# Max3100Uart.net
KiCad netlist of a schematic drawn in Altium Designer
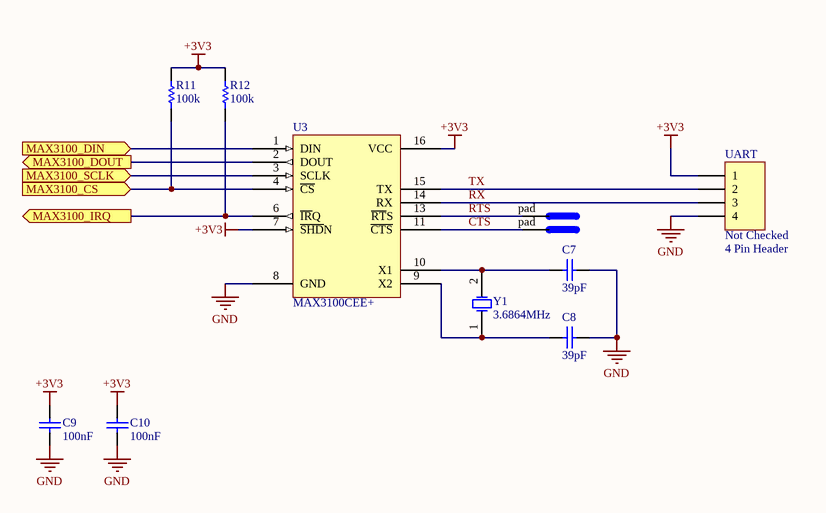
[diagram p0: Max3100Uart.SchDoc]

(export (version "E")
  (design (tool "Eeschema 10.0.6"))
  (components
    (comp (ref "C7")
      (value "39pF")
      (footprint "0603")
      (description "Capacitor")
      (fields (field (name "Comment") "Cap") (field (name "PUBLISHER") "Altium Limited"))
      (libsource (lib "Miscellaneous Devices") (part "Cap"))
    )
    (comp (ref "C8")
      (value "39pF")
      (footprint "0603")
      (description "Capacitor")
      (fields (field (name "Comment") "Cap") (field (name "PUBLISHER") "Altium Limited"))
      (libsource (lib "Miscellaneous Devices") (part "Cap"))
    )
    (comp (ref "C9")
      (value "100nF")
      (footprint "GRC PCB library:0603")
      (description "CAP CER .10UF 50V X5R 0603")
      (fields (field (name "MANUFACTURER") "Taiyo Yuden"))
      (libsource (lib "GRC sch library") (part "CP_100nF 0603"))
    )
    (comp (ref "C10")
      (value "100nF")
      (footprint "GRC PCB library:0603")
      (description "CAP CER .10UF 50V X5R 0603")
      (fields (field (name "MANUFACTURER") "Taiyo Yuden"))
      (libsource (lib "GRC sch library") (part "CP_100nF 0603"))
    )
    (comp (ref "CTS")
      (value "~")
      (footprint "PAD_ROUND")
      (description "Pad")
      (libsource (lib "GRC sch library") (part "JP_pad"))
    )
    (comp (ref "R11")
      (value "100k")
      (footprint "GRC PCB library:0603")
      (description "RES 100K OHM 1/10W 1% 0603 SMD")
      (fields (field (name "MANUFACTURER") "Yageo"))
      (libsource (lib "GRC sch library") (part "RS_100k 0603"))
    )
    (comp (ref "R12")
      (value "100k")
      (footprint "GRC PCB library:0603")
      (description "RES 100K OHM 1/10W 1% 0603 SMD")
      (fields (field (name "MANUFACTURER") "Yageo"))
      (libsource (lib "GRC sch library") (part "RS_100k 0603"))
    )
    (comp (ref "RTS")
      (value "~")
      (footprint "PAD_ROUND")
      (description "Pad")
      (libsource (lib "GRC sch library") (part "JP_pad"))
    )
    (comp (ref "U3")
      (value "MAX3100CEE+")
      (footprint "QSOP16_MAX3100")
      (description "SPI UART")
      (libsource (lib "GRC sch library") (part "IC_MAX3100"))
    )
    (comp (ref "UART")
      (value "4 Pin Header")
      (footprint "CONN_4X1_SMT_RA_1.25MM")
      (description "CONN HDR VERT 4POS .100\" SNGL")
      (fields (field (name "MANUFACTURER") "Molex") (field (name "VERIFY") "Not Checked"))
      (libsource (lib "GRC sch library") (part "JP_4PIN HDR_SMT_RA_MOLEX_1"))
    )
    (comp (ref "Y1")
      (value "3.6864MHz")
      (footprint "HC49/4h_SMX")
      (description "Crystal Oscillator")
      (fields (field (name "MANUFACTURER") "ECS") (field (name "PUBLISHER") "Altium Limited"))
      (libsource (lib "Miscellaneous Devices") (part "XTAL"))
    )
  )
  (nets
    (net (code "1") (name "+3V3") (class "Default")
      (node (ref "C10") (pin "2") (pinfunction "2_2") (pintype "passive"))
      (node (ref "C9") (pin "2") (pinfunction "2_2") (pintype "passive"))
      (node (ref "R11") (pin "2") (pinfunction "2_2") (pintype "passive"))
      (node (ref "R12") (pin "2") (pinfunction "2_2") (pintype "passive"))
      (node (ref "U3") (pin "16") (pinfunction "VCC_16") (pintype "power_in"))
      (node (ref "U3") (pin "7") (pinfunction "~{SHD}N_7") (pintype "input"))
      (node (ref "UART") (pin "1") (pinfunction "1_1") (pintype "passive"))
    )
    (net (code "2") (name "/CTS") (class "Default")
      (node (ref "CTS") (pin "pad") (pintype "passive"))
      (node (ref "U3") (pin "11") (pinfunction "~{CTS}_11") (pintype "passive"))
    )
    (net (code "3") (name "/MAX3100_CS") (class "Default")
      (node (ref "R11") (pin "1") (pinfunction "1_1") (pintype "passive"))
      (node (ref "U3") (pin "4") (pinfunction "~{CS}_4") (pintype "input"))
    )
    (net (code "4") (name "/MAX3100_DIN") (class "Default")
      (node (ref "U3") (pin "1") (pinfunction "DIN_1") (pintype "input"))
    )
    (net (code "5") (name "/MAX3100_DOUT") (class "Default")
      (node (ref "U3") (pin "2") (pinfunction "DOUT_2") (pintype "output"))
    )
    (net (code "6") (name "/MAX3100_IRQ") (class "Default")
      (node (ref "R12") (pin "1") (pinfunction "1_1") (pintype "passive"))
      (node (ref "U3") (pin "6") (pinfunction "~{IR}Q_6") (pintype "output"))
    )
    (net (code "7") (name "/MAX3100_SCLK") (class "Default")
      (node (ref "U3") (pin "3") (pinfunction "SCLK_3") (pintype "input"))
    )
    (net (code "8") (name "/RTS") (class "Default")
      (node (ref "RTS") (pin "pad") (pintype "passive"))
      (node (ref "U3") (pin "13") (pinfunction "~{RT}S_13") (pintype "passive"))
    )
    (net (code "9") (name "/RX") (class "Default")
      (node (ref "U3") (pin "14") (pinfunction "RX_14") (pintype "passive"))
      (node (ref "UART") (pin "3") (pinfunction "3_3") (pintype "passive"))
    )
    (net (code "10") (name "/TX") (class "Default")
      (node (ref "U3") (pin "15") (pinfunction "TX_15") (pintype "passive"))
      (node (ref "UART") (pin "2") (pinfunction "2_2") (pintype "passive"))
    )
    (net (code "11") (name "GND") (class "Default")
      (node (ref "C10") (pin "1") (pinfunction "1_1") (pintype "passive"))
      (node (ref "C7") (pin "2") (pinfunction "2_2") (pintype "passive"))
      (node (ref "C8") (pin "1") (pinfunction "1_1") (pintype "passive"))
      (node (ref "C9") (pin "1") (pinfunction "1_1") (pintype "passive"))
      (node (ref "U3") (pin "8") (pinfunction "GND_8") (pintype "power_in"))
      (node (ref "UART") (pin "4") (pinfunction "4_4") (pintype "passive"))
    )
    (net (code "12") (name "Net-(U3-X1)") (class "Default")
      (node (ref "C7") (pin "1") (pinfunction "1_1") (pintype "passive"))
      (node (ref "U3") (pin "10") (pinfunction "X1_10") (pintype "passive"))
      (node (ref "Y1") (pin "2") (pinfunction "OSC2_2") (pintype "passive"))
    )
    (net (code "13") (name "Net-(U3-X2)") (class "Default")
      (node (ref "C8") (pin "2") (pinfunction "2_2") (pintype "passive"))
      (node (ref "U3") (pin "9") (pinfunction "X2_9") (pintype "passive"))
      (node (ref "Y1") (pin "1") (pinfunction "OSC1_1") (pintype "passive"))
    )
  )
)
